# USB-C_INTERFACE.net
KiCad netlist of a schematic drawn in Altium Designer
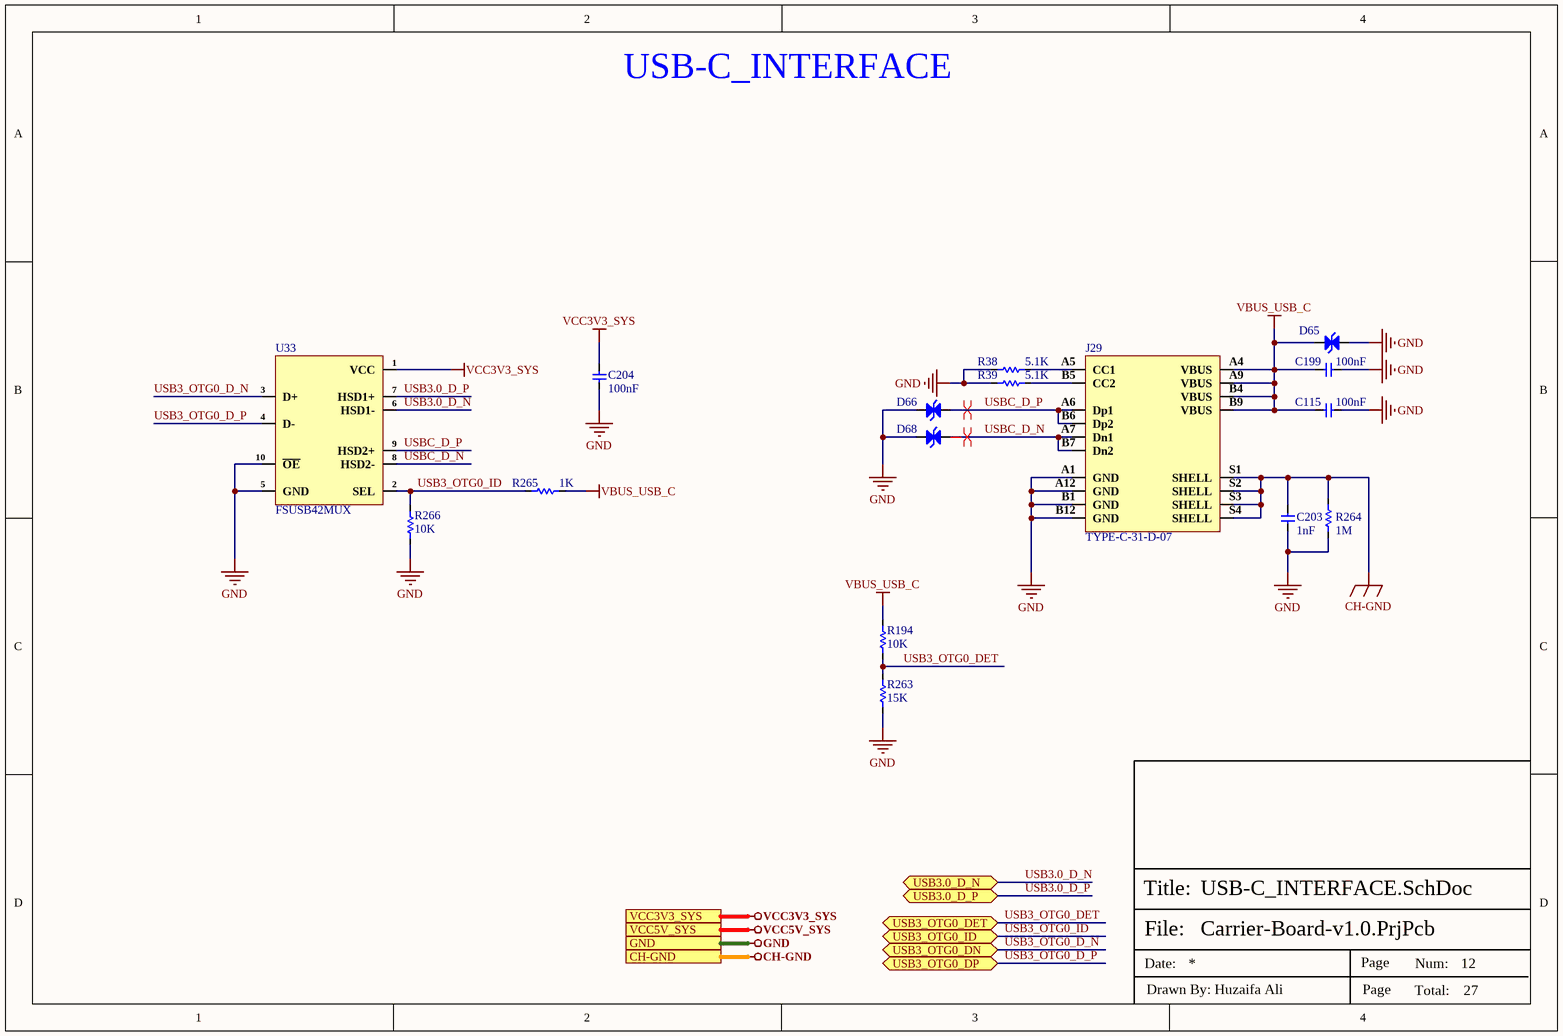
[diagram p0: USB-C_INTERFACE.SchDoc]

(export (version "E")
  (design (tool "Eeschema 10.0.6"))
  (components
    (comp (ref "C115")
      (value "100nF")
      (footprint "Cap-0402")
      (description "CAP CER 0.1UF 16V X5R 0402")
      (fields
        (field (name "MANUFACTURER") "Yageo")
        (field (name "MANUFACTURER PART NUMBER") "CC0402KRX5R7BB104")
      )
      (libsource (lib "eSpark Libraries") (part "CC0402KRX5R7BB104"))
    )
    (comp (ref "C199")
      (value "100nF")
      (footprint "Cap-0402")
      (description "CAP CER 0.1UF 16V X5R 0402")
      (fields
        (field (name "MANUFACTURER") "Yageo")
        (field (name "MANUFACTURER PART NUMBER") "CC0402KRX5R7BB104")
      )
      (libsource (lib "eSpark Libraries") (part "CC0402KRX5R7BB104"))
    )
    (comp (ref "C203")
      (value "1nF")
      (footprint "Cap-1206")
      (description "CAP CER 1000PF 2KV X7R 1206")
      (fields
        (field (name "MANUFACTURER") "Yageo")
        (field (name "MANUFACTURER PART NUMBER") "CC1206KKX7RDBB102")
      )
      (libsource (lib "eSpark Libraries") (part "CC1206KKX7RDBB102"))
    )
    (comp (ref "C204")
      (value "100nF")
      (footprint "Cap-0402")
      (description "CAP CER 0.1UF 16V X5R 0402")
      (fields
        (field (name "MANUFACTURER") "Yageo")
        (field (name "MANUFACTURER PART NUMBER") "CC0402KRX5R7BB104")
      )
      (libsource (lib "eSpark Libraries") (part "CC0402KRX5R7BB104"))
    )
    (comp (ref "D65")
      (value "ESD5451N")
      (footprint "DFN1006-2L (Bi-Directional)")
      (description "DFN1006-2(0402) ESD Protection Devices ROHS")
      (fields (field (name "MANUFACTURER") "TECH PUBLIC") (field (name "LCSC PART NUMBER") "C2936977"))
      (libsource (lib "eSpark Libraries") (part "ESD5451N"))
    )
    (comp (ref "D66")
      (value "ESD5451N")
      (footprint "DFN1006-2L (Bi-Directional)")
      (description "DFN1006-2(0402) ESD Protection Devices ROHS")
      (fields (field (name "MANUFACTURER") "TECH PUBLIC") (field (name "LCSC PART NUMBER") "C2936977"))
      (libsource (lib "eSpark Libraries") (part "ESD5451N"))
    )
    (comp (ref "D68")
      (value "ESD5451N")
      (footprint "DFN1006-2L (Bi-Directional)")
      (description "DFN1006-2(0402) ESD Protection Devices ROHS")
      (fields (field (name "MANUFACTURER") "TECH PUBLIC") (field (name "LCSC PART NUMBER") "C2936977"))
      (libsource (lib "eSpark Libraries") (part "ESD5451N"))
    )
    (comp (ref "J29")
      (value "TYPE-C-31-D-07")
      (footprint "TYPE-C-31-D-07")
      (description "1 Brick nogging 14P Female Type-C SMD USB Connectors ROHS")
      (fields (field (name "MANUFACTURER") "Korean Hroparts Elec"))
      (libsource (lib "eSpark Libraries") (part "TYPE-C-31-D-07"))
    )
    (comp (ref "R38")
      (value "5.1K")
      (footprint "Res-0402")
      (description "RES 5.1K OHM 1% 1/16W 0402")
      (fields
        (field (name "MANUFACTURER") "Yageo")
        (field (name "MANUFACTURER PART NUMBER") "RC0402FR-075K1L")
      )
      (libsource (lib "eSpark Libraries") (part "RC0402FR-075K1L"))
    )
    (comp (ref "R39")
      (value "5.1K")
      (footprint "Res-0402")
      (description "RES 5.1K OHM 1% 1/16W 0402")
      (fields
        (field (name "MANUFACTURER") "Yageo")
        (field (name "MANUFACTURER PART NUMBER") "RC0402FR-075K1L")
      )
      (libsource (lib "eSpark Libraries") (part "RC0402FR-075K1L"))
    )
    (comp (ref "R194")
      (value "10K")
      (footprint "Res-0402")
      (description "RES 10K OHM 1% 1/16W 0402")
      (fields
        (field (name "MANUFACTURER") "Yageo")
        (field (name "MANUFACTURER PART NUMBER") "RC0402FR-0710KL")
      )
      (libsource (lib "eSpark Libraries") (part "RC0402FR-0710KL"))
    )
    (comp (ref "R263")
      (value "15K")
      (footprint "Res-0402")
      (description "RES SMD 15K OHM 0.1% 1/16W 0402")
      (fields
        (field (name "MANUFACTURER") "Yageo")
        (field (name "MANUFACTURER PART NUMBER") "RT0402BRD0715KL")
      )
      (libsource (lib "eSpark Libraries") (part "RT0402BRD0715KL"))
    )
    (comp (ref "R264")
      (value "1M")
      (footprint "Res-0402")
      (description "RES SMD 1M OHM 5% 1/16W 0402")
      (fields
        (field (name "MANUFACTURER") "Yageo")
        (field (name "MANUFACTURER PART NUMBER") "AF0402JR-071ML")
      )
      (libsource (lib "eSpark Libraries") (part "AF0402JR-071ML"))
    )
    (comp (ref "R265")
      (value "1K")
      (footprint "Res-0402")
      (description "RES 1K OHM 1% 1/16W 0402")
      (fields
        (field (name "MANUFACTURER") "Yageo")
        (field (name "MANUFACTURER PART NUMBER") "RC0402FR-071KL")
      )
      (libsource (lib "eSpark Libraries") (part "RC0402FR-071KL"))
    )
    (comp (ref "R266")
      (value "10K")
      (footprint "Res-0402")
      (description "RES 10K OHM 1% 1/16W 0402")
      (fields
        (field (name "MANUFACTURER") "Yageo")
        (field (name "MANUFACTURER PART NUMBER") "RC0402FR-0710KL")
      )
      (libsource (lib "eSpark Libraries") (part "RC0402FR-0710KL"))
    )
    (comp (ref "U33")
      (value "FSUSB42MUX")
      (footprint "10-MSOP")
      (description "IC USB SWITCH DPDT 10MSOP")
      (fields
        (field (name "MANUFACTURER") "ON Semiconductor / Fairchild")
        (field (name "LCSC PART NUMBER") "C11355")
      )
      (libsource (lib "eSpark Libraries") (part "FSUSB42MUX"))
    )
  )
  (nets
    (net (code "1") (name "/USB3.0_D_N") (class "Default")
      (node (ref "U33") (pin "6") (pinfunction "HSD1-_6") (pintype "passive"))
    )
    (net (code "2") (name "/USB3.0_D_P") (class "Default")
      (node (ref "U33") (pin "7") (pinfunction "HSD1+_7") (pintype "passive"))
    )
    (net (code "3") (name "/USB3_OTG0_DET") (class "Default")
      (node (ref "R194") (pin "2") (pinfunction "2_2") (pintype "passive"))
      (node (ref "R263") (pin "2") (pinfunction "2_2") (pintype "passive"))
    )
    (net (code "4") (name "/USB3_OTG0_D_N") (class "Default")
      (node (ref "U33") (pin "3") (pinfunction "D+_3") (pintype "passive"))
    )
    (net (code "5") (name "/USB3_OTG0_D_P") (class "Default")
      (node (ref "U33") (pin "4") (pinfunction "D-_4") (pintype "passive"))
    )
    (net (code "6") (name "/USB3_OTG0_ID") (class "Default")
      (node (ref "R265") (pin "1") (pinfunction "1_1") (pintype "passive"))
      (node (ref "R266") (pin "1") (pinfunction "1_1") (pintype "passive"))
      (node (ref "U33") (pin "2") (pinfunction "SEL_2") (pintype "passive"))
    )
    (net (code "7") (name "/USBC_D_N") (class "Default")
      (node (ref "D68") (pin "1") (pinfunction "K_1") (pintype "passive"))
      (node (ref "J29") (pin "A7") (pinfunction "Dn1_A7") (pintype "passive"))
      (node (ref "J29") (pin "B7") (pinfunction "Dn2_B7") (pintype "passive"))
      (node (ref "U33") (pin "8") (pinfunction "HSD2-_8") (pintype "passive"))
    )
    (net (code "8") (name "/USBC_D_P") (class "Default")
      (node (ref "D66") (pin "1") (pinfunction "K_1") (pintype "passive"))
      (node (ref "J29") (pin "A6") (pinfunction "Dp1_A6") (pintype "passive"))
      (node (ref "J29") (pin "B6") (pinfunction "Dp2_B6") (pintype "passive"))
      (node (ref "U33") (pin "9") (pinfunction "HSD2+_9") (pintype "passive"))
    )
    (net (code "9") (name "CH-GND") (class "Default")
      (node (ref "C203") (pin "2") (pinfunction "2_2") (pintype "passive"))
      (node (ref "J29") (pin "S1") (pinfunction "SHELL_S1") (pintype "passive"))
      (node (ref "J29") (pin "S2") (pinfunction "SHELL_S2") (pintype "passive"))
      (node (ref "J29") (pin "S3") (pinfunction "SHELL_S3") (pintype "passive"))
      (node (ref "J29") (pin "S4") (pinfunction "SHELL_S4") (pintype "passive"))
      (node (ref "R264") (pin "2") (pinfunction "2_2") (pintype "passive"))
    )
    (net (code "10") (name "GND") (class "Default")
      (node (ref "C115") (pin "1") (pinfunction "1_1") (pintype "passive"))
      (node (ref "C199") (pin "1") (pinfunction "1_1") (pintype "passive"))
      (node (ref "C203") (pin "1") (pinfunction "1_1") (pintype "passive"))
      (node (ref "C204") (pin "1") (pinfunction "1_1") (pintype "passive"))
      (node (ref "D65") (pin "1") (pinfunction "K_1") (pintype "passive"))
      (node (ref "D66") (pin "2") (pinfunction "K_2") (pintype "passive"))
      (node (ref "D68") (pin "2") (pinfunction "K_2") (pintype "passive"))
      (node (ref "J29") (pin "A1") (pinfunction "GND_A1") (pintype "power_in"))
      (node (ref "J29") (pin "A12") (pinfunction "GND_A12") (pintype "power_in"))
      (node (ref "J29") (pin "B1") (pinfunction "GND_B1") (pintype "power_in"))
      (node (ref "J29") (pin "B12") (pinfunction "GND_B12") (pintype "power_in"))
      (node (ref "R263") (pin "1") (pinfunction "1_1") (pintype "passive"))
      (node (ref "R264") (pin "1") (pinfunction "1_1") (pintype "passive"))
      (node (ref "R266") (pin "2") (pinfunction "2_2") (pintype "passive"))
      (node (ref "R38") (pin "1") (pinfunction "1_1") (pintype "passive"))
      (node (ref "R39") (pin "1") (pinfunction "1_1") (pintype "passive"))
      (node (ref "U33") (pin "10") (pinfunction "~{OE}_10") (pintype "passive"))
      (node (ref "U33") (pin "5") (pinfunction "GND_5") (pintype "passive"))
    )
    (net (code "11") (name "Net-(J29-CC1)") (class "Default")
      (node (ref "J29") (pin "A5") (pinfunction "CC1_A5") (pintype "passive"))
      (node (ref "R38") (pin "2") (pinfunction "2_2") (pintype "passive"))
    )
    (net (code "12") (name "Net-(J29-CC2)") (class "Default")
      (node (ref "J29") (pin "B5") (pinfunction "CC2_B5") (pintype "passive"))
      (node (ref "R39") (pin "2") (pinfunction "2_2") (pintype "passive"))
    )
    (net (code "13") (name "VBUS_USB_C") (class "Default")
      (node (ref "C115") (pin "2") (pinfunction "2_2") (pintype "passive"))
      (node (ref "C199") (pin "2") (pinfunction "2_2") (pintype "passive"))
      (node (ref "D65") (pin "2") (pinfunction "K_2") (pintype "passive"))
      (node (ref "J29") (pin "A4") (pinfunction "VBUS_A4") (pintype "power_in"))
      (node (ref "J29") (pin "A9") (pinfunction "VBUS_A9") (pintype "power_in"))
      (node (ref "J29") (pin "B4") (pinfunction "VBUS_B4") (pintype "power_in"))
      (node (ref "J29") (pin "B9") (pinfunction "VBUS_B9") (pintype "power_in"))
      (node (ref "R194") (pin "1") (pinfunction "1_1") (pintype "passive"))
      (node (ref "R265") (pin "2") (pinfunction "2_2") (pintype "passive"))
    )
    (net (code "14") (name "VCC3V3_SYS") (class "Default")
      (node (ref "C204") (pin "2") (pinfunction "2_2") (pintype "passive"))
      (node (ref "U33") (pin "1") (pinfunction "VCC_1") (pintype "passive"))
    )
  )
)
